# Power_Suply.net
KiCad netlist of a schematic drawn in Altium Designer
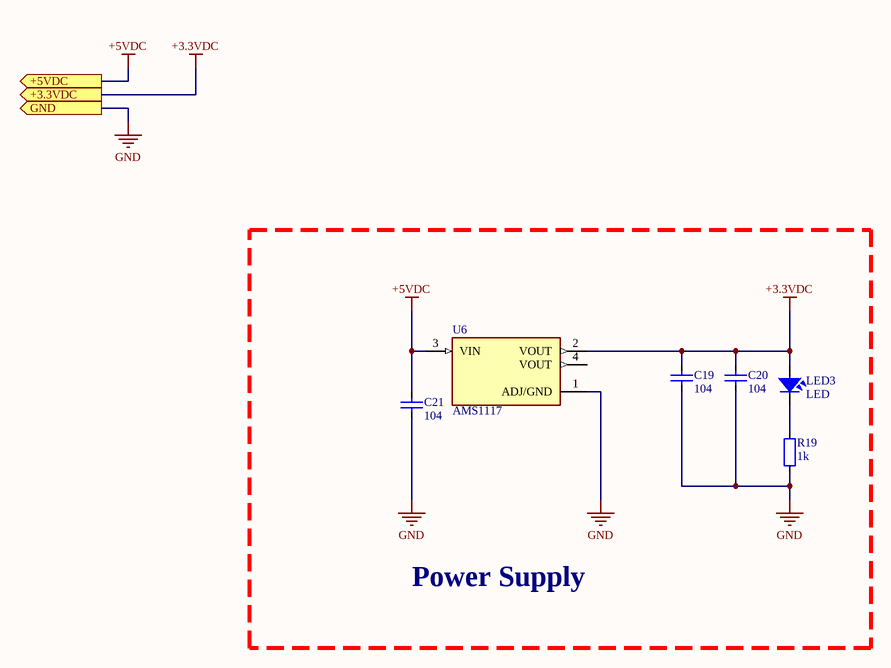
[diagram p0: Power_Suply.SchDoc]

(export (version "E")
  (design (tool "Eeschema 10.0.6"))
  (components
    (comp (ref "C19")
      (value "104")
      (footprint "CAP_0805")
      (description "Capacitor")
      (fields (field (name "PUBLISHER") "Altium Limited"))
      (libsource (lib "My Library") (part "CapSMD"))
    )
    (comp (ref "C20")
      (value "104")
      (footprint "CAP_0805")
      (description "Capacitor")
      (fields (field (name "PUBLISHER") "Altium Limited"))
      (libsource (lib "My Library") (part "CapSMD"))
    )
    (comp (ref "C21")
      (value "104")
      (footprint "CAP_0805")
      (description "Capacitor")
      (fields (field (name "PUBLISHER") "Altium Limited"))
      (libsource (lib "My Library") (part "CapSMD"))
    )
    (comp (ref "LED3")
      (value "LED")
      (footprint "LED-0805-Red")
      (description "LED Single colour Green and Red")
      (libsource (lib "My Library") (part "LED"))
    )
    (comp (ref "R19")
      (value "1k")
      (footprint "RES-SMD-0805")
      (description "Resistor")
      (fields
        (field (name "MANUFACTURER") "Generic Components")
        (field (name "PUBLISHER") "Altium Hobart Technology Centre")
      )
      (libsource (lib "My Library") (part "Resistor - SMD"))
    )
    (comp (ref "U6")
      (value "AMS1117")
      (footprint "SOT229P700X180-4N")
      (description "1A LOW DROPOUT VOLTAGE REGULATOR SOT-223")
      (fields (field (name "MF") "Advanced Monolithic Systems"))
      (libsource (lib "AMS1117") (part "AMS1117"))
    )
  )
  (nets
    (net (code "1") (name "+3.3VDC") (class "Default")
      (node (ref "C19") (pin "2") (pinfunction "2_2") (pintype "passive"))
      (node (ref "C20") (pin "2") (pinfunction "2_2") (pintype "passive"))
      (node (ref "LED3") (pin "1") (pinfunction "1_1") (pintype "passive"))
      (node (ref "U6") (pin "2") (pinfunction "VOUT_2") (pintype "output"))
    )
    (net (code "2") (name "+5VDC") (class "Default")
      (node (ref "C21") (pin "2") (pinfunction "2_2") (pintype "passive"))
      (node (ref "U6") (pin "3") (pinfunction "VIN_3") (pintype "input"))
    )
    (net (code "3") (name "GND") (class "Default")
      (node (ref "C19") (pin "1") (pinfunction "1_1") (pintype "passive"))
      (node (ref "C20") (pin "1") (pinfunction "1_1") (pintype "passive"))
      (node (ref "C21") (pin "1") (pinfunction "1_1") (pintype "passive"))
      (node (ref "R19") (pin "1") (pinfunction "1_1") (pintype "passive"))
      (node (ref "U6") (pin "1") (pinfunction "ADJ/GND_1") (pintype "power_in"))
    )
    (net (code "4") (name "Net-(LED3-Pad2)") (class "Default")
      (node (ref "LED3") (pin "2") (pinfunction "2_2") (pintype "passive"))
      (node (ref "R19") (pin "2") (pinfunction "2_2") (pintype "passive"))
    )
    (net (code "5") (name "unconnected-(U6-VOUT-Pad4)") (class "Default")
      (node (ref "U6") (pin "4") (pinfunction "VOUT_4") (pintype "output"))
    )
  )
)
